# Analog_PI_Controller_v7.net
KiCad netlist of a schematic drawn in EasyEDA
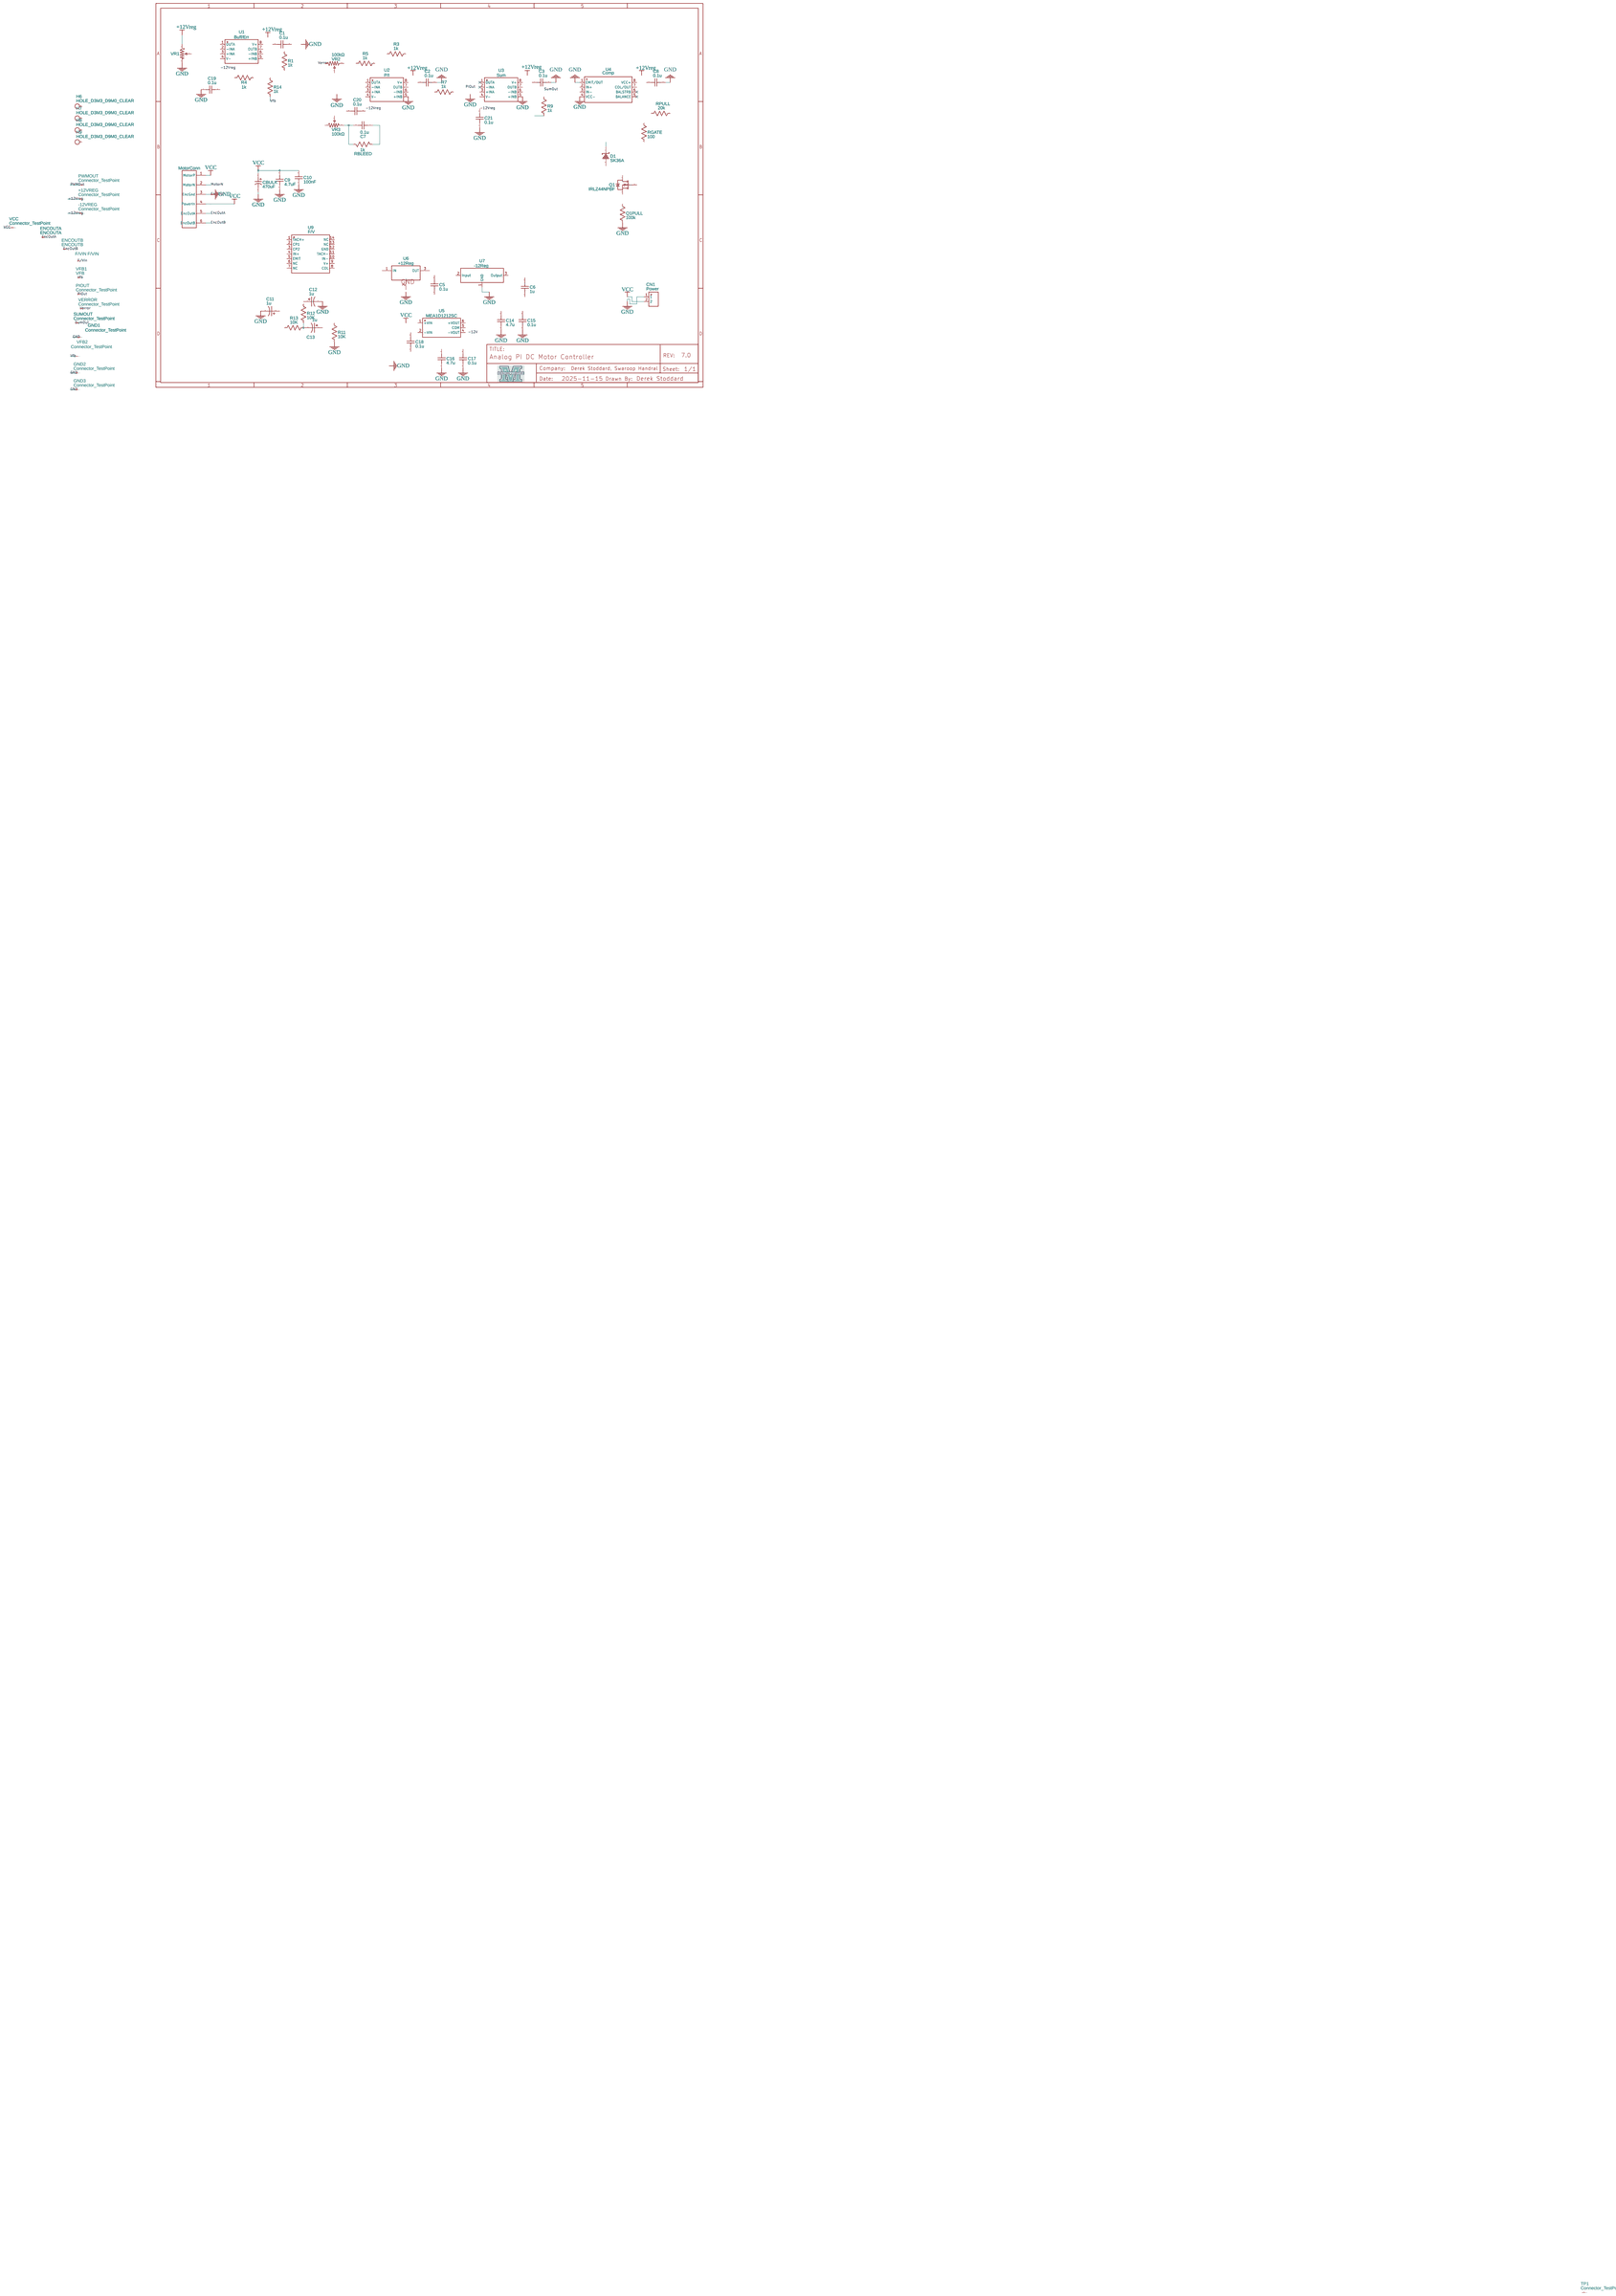
[diagram p0: schematic sheet]

(export (version "E")
  (design (tool "Eeschema 10.0.6"))
  (components
    (comp (ref "+12VREG") (value "Connector_TestPoint") (libsource (lib "") (part "Connector_TestPoint_8")))
    (comp (ref "-12VREG") (value "Connector_TestPoint") (libsource (lib "") (part "Connector_TestPoint_9")))
    (comp (ref "C1") (value "0.1u") (libsource (lib "") (part "C_0603_US_1")))
    (comp (ref "C2") (value "0.1u") (libsource (lib "") (part "C_0603_US_1")))
    (comp (ref "C3") (value "0.1u") (libsource (lib "") (part "C_0603_US_1")))
    (comp (ref "C5") (value "0.1u") (libsource (lib "") (part "C_0603_US")))
    (comp (ref "C6") (value "1u") (libsource (lib "") (part "C_0603_US")))
    (comp (ref "C7") (value "0.1u") (libsource (lib "") (part "C_0603_US_2")))
    (comp (ref "C8") (value "0.1u") (libsource (lib "") (part "C_0603_US_1")))
    (comp (ref "C9")
      (value "4.7uF")
      (fields
        (field (name "Manufacturer Part") "GRM188R61E475KE11D")
        (field (name "Manufacturer") "muRata(村田)")
      )
      (libsource (lib "") (part "GRM188R61E475KE11D"))
    )
    (comp (ref "C10")
      (value "100nF")
      (fields
        (field (name "Manufacturer Part") "GRM033R61E104KE14D")
        (field (name "Manufacturer") "muRata(村田)")
      )
      (libsource (lib "") (part "GRM033R61E104KE14D"))
    )
    (comp (ref "C11") (value "1u") (libsource (lib "") (part "C_Tan_SMD_A_US_2")))
    (comp (ref "C12") (value "1u") (libsource (lib "") (part "C_Tan_SMD_A_US_1")))
    (comp (ref "C13") (value "1u") (libsource (lib "") (part "C_Tan_SMD_A_US")))
    (comp (ref "C14") (value "4.7u") (libsource (lib "") (part "C_0603_US")))
    (comp (ref "C15") (value "0.1u") (libsource (lib "") (part "C_0603_US")))
    (comp (ref "C16") (value "4.7u") (libsource (lib "") (part "C_0603_US")))
    (comp (ref "C17") (value "0.1u") (libsource (lib "") (part "C_0603_US")))
    (comp (ref "C18") (value "0.1u") (libsource (lib "") (part "C_0603_US")))
    (comp (ref "C19") (value "0.1u") (libsource (lib "") (part "C_0603_US_1")))
    (comp (ref "C20") (value "0.1u") (libsource (lib "") (part "C_0603_US_1")))
    (comp (ref "C21") (value "0.1u") (libsource (lib "") (part "C_0603_US")))
    (comp (ref "CBULK")
      (value "470uF")
      (fields (field (name "Manufacturer Part") "EEEFN1V471UP") (field (name "Manufacturer") "PANASONIC(松下)"))
      (libsource (lib "") (part "EEEFN1V471UP"))
    )
    (comp (ref "CN1")
      (value "Power")
      (fields (field (name "Manufacturer Part") "691137710002") (field (name "Manufacturer") "Wurth(伍尔特)"))
      (libsource (lib "") (part "691137710002"))
    )
    (comp (ref "D1")
      (value "SK36A")
      (fields (field (name "Manufacturer Part") "SK36A-LTP") (field (name "Manufacturer") "MCC(美微科)"))
      (libsource (lib "") (part "SK36A-LTP"))
    )
    (comp (ref "ENCOUTA") (value "ENCOUTA") (libsource (lib "") (part "Connector_TestPoint_2")))
    (comp (ref "ENCOUTB") (value "ENCOUTB") (libsource (lib "") (part "Connector_TestPoint_1")))
    (comp (ref "F/VIN") (value "F/VIN") (libsource (lib "") (part "Connector_TestPoint_11")))
    (comp (ref "GND1") (value "Connector_TestPoint") (libsource (lib "") (part "Connector_TestPoint_4")))
    (comp (ref "GND2") (value "Connector_TestPoint") (libsource (lib "") (part "Connector_TestPoint_4")))
    (comp (ref "GND3") (value "Connector_TestPoint") (libsource (lib "") (part "Connector_TestPoint_4")))
    (comp (ref "H6") (value "HOLE_D3M3_D9M0_CLEAR") (libsource (lib "") (part "HOLE_D3M3_D9M0_CLEAR")))
    (comp (ref "H7") (value "HOLE_D3M3_D9M0_CLEAR") (libsource (lib "") (part "HOLE_D3M3_D9M0_CLEAR")))
    (comp (ref "H8") (value "HOLE_D3M3_D9M0_CLEAR") (libsource (lib "") (part "HOLE_D3M3_D9M0_CLEAR")))
    (comp (ref "H9") (value "HOLE_D3M3_D9M0_CLEAR") (libsource (lib "") (part "HOLE_D3M3_D9M0_CLEAR")))
    (comp (ref "MIN")
      (value "MotorConn")
      (fields (field (name "Manufacturer Part") "14110613002000") (field (name "Manufacturer") "Harting"))
      (libsource (lib "") (part "Harting 6P vertical"))
    )
    (comp (ref "PIOUT") (value "Connector_TestPoint") (libsource (lib "") (part "Connector_TestPoint_10")))
    (comp (ref "PWMOUT") (value "Connector_TestPoint") (libsource (lib "") (part "Connector_TestPoint_12")))
    (comp (ref "Q1")
      (value "IRLZ44NPBF")
      (fields (field (name "Manufacturer") "Infineon(英飞凌)"))
      (libsource (lib "") (part "IRLZ44NPBF"))
    )
    (comp (ref "Q1PULL") (value "100k") (libsource (lib "") (part "R_0603_US_6")))
    (comp (ref "R1") (value "1k") (libsource (lib "") (part "R_0603_US_2")))
    (comp (ref "R3") (value "1k") (libsource (lib "") (part "R_0603_US_1")))
    (comp (ref "R4") (value "1k") (libsource (lib "") (part "R_0603_US_5")))
    (comp (ref "R5") (value "1k") (libsource (lib "") (part "R_0603_US_1")))
    (comp (ref "R7") (value "1k") (libsource (lib "") (part "R_0603_US_5")))
    (comp (ref "R9") (value "1k") (libsource (lib "") (part "R_0603_US")))
    (comp (ref "R11") (value "10K") (libsource (lib "") (part "R_0603_US_2")))
    (comp (ref "R12") (value "10K") (libsource (lib "") (part "R_0603_US_2")))
    (comp (ref "R13") (value "10K") (libsource (lib "") (part "R_0603_US_1")))
    (comp (ref "R14") (value "1k") (libsource (lib "") (part "R_0603_US_2")))
    (comp (ref "RBLEED") (value "1k") (libsource (lib "") (part "R_0603_US_3")))
    (comp (ref "RGATE") (value "100") (libsource (lib "") (part "R_0603_US_7")))
    (comp (ref "RPULL") (value "20k") (libsource (lib "") (part "R_0603_US_4")))
    (comp (ref "SUMOUT") (value "Connector_TestPoint") (libsource (lib "") (part "Connector_TestPoint_5")))
    (comp (ref "TP1") (value "Connector_TestPoint") (libsource (lib "") (part "Connector_TestPoint_3")))
    (comp (ref "U1")
      (value "Buff/Err")
      (fields (field (name "Manufacturer Part") "OPA2197ID") (field (name "Manufacturer") "TI(德州仪器)"))
      (libsource (lib "") (part "OPA2197ID"))
    )
    (comp (ref "U2")
      (value "P/I")
      (fields (field (name "Manufacturer Part") "OPA2197ID") (field (name "Manufacturer") "TI(德州仪器)"))
      (libsource (lib "") (part "OPA2197ID"))
    )
    (comp (ref "U3")
      (value "Sum")
      (fields (field (name "Manufacturer Part") "OPA2197ID") (field (name "Manufacturer") "TI(德州仪器)"))
      (libsource (lib "") (part "OPA2197ID"))
    )
    (comp (ref "U4")
      (value "Comp")
      (fields (field (name "Manufacturer Part") "LM311DR") (field (name "Manufacturer") "TI(德州仪器)"))
      (libsource (lib "") (part "LM311DR"))
    )
    (comp (ref "U5")
      (value "MEA1D1212SC")
      (fields (field (name "Manufacturer") "YLPTEC(易川)"))
      (libsource (lib "") (part "MEA1D1212SC"))
    )
    (comp (ref "U6")
      (value "+12Reg")
      (fields (field (name "Manufacturer Part") "LM7812CT/NOPB") (field (name "Manufacturer") "TI(德州仪器)"))
      (libsource (lib "") (part "LM7812CT/NOPB"))
    )
    (comp (ref "U7")
      (value "-12Reg")
      (fields (field (name "Manufacturer Part") "LM7912CT/NOPB") (field (name "Manufacturer") "TI(德州仪器)"))
      (libsource (lib "") (part "LM7912CT/NOPB"))
    )
    (comp (ref "U9")
      (value "F/V")
      (fields (field (name "Manufacturer Part") "LM2917MX/NOPB") (field (name "Manufacturer") "TI(德州仪器)"))
      (libsource (lib "") (part "LM2917MX/NOPB"))
    )
    (comp (ref "VCC") (value "Connector_TestPoint") (libsource (lib "") (part "Connector_TestPoint_7")))
    (comp (ref "VERROR") (value "Connector_TestPoint") (libsource (lib "") (part "Connector_TestPoint_6")))
    (comp (ref "VFB1") (value "VFB") (libsource (lib "") (part "Connector_TestPoint")))
    (comp (ref "VFB2") (value "Connector_TestPoint") (libsource (lib "") (part "Connector_TestPoint")))
    (comp (ref "VR1")
      (value "PTV09A-4020U-B104")
      (fields (field (name "Manufacturer") "Bourns Inc."))
      (libsource (lib "") (part "PTV09A-4020U-B104"))
    )
    (comp (ref "VR2")
      (value "100kΩ")
      (fields (field (name "Manufacturer Part") "PVG5A104C03R00") (field (name "Manufacturer") "BOURNS"))
      (libsource (lib "") (part "PVG5A104C03R00"))
    )
    (comp (ref "VR3")
      (value "100kΩ")
      (fields (field (name "Manufacturer Part") "PVG5A104C03R00") (field (name "Manufacturer") "BOURNS"))
      (libsource (lib "") (part "PVG5A104C03R00_1"))
    )
  )
  (nets
    (net (code "1") (name "+12Vreg") (class "Default")
      (node (ref "+12VREG") (pin "1") (pinfunction "1_1") (pintype "unspecified"))
      (node (ref "VR1") (pin "1") (pinfunction "1_1") (pintype "unspecified"))
    )
    (net (code "3") (name "/-12Vreg") (class "Default")
      (node (ref "-12VREG") (pin "1") (pinfunction "1_1") (pintype "unspecified"))
      (node (ref "C21") (pin "2") (pinfunction "2_2") (pintype "unspecified"))
    )
    (net (code "4") (name "/EncOutA") (class "Default")
      (node (ref "ENCOUTA") (pin "1") (pinfunction "1_1") (pintype "unspecified"))
      (node (ref "MIN") (pin "5") (pinfunction "EncOutA_5") (pintype "output"))
    )
    (net (code "5") (name "/EncOutB") (class "Default")
      (node (ref "ENCOUTB") (pin "1") (pinfunction "1_1") (pintype "unspecified"))
      (node (ref "MIN") (pin "6") (pinfunction "EncOutB_6") (pintype "output"))
    )
    (net (code "6") (name "/F{slash}VIn") (class "Default")
      (node (ref "F/VIN") (pin "1") (pinfunction "1_1") (pintype "unspecified"))
    )
    (net (code "7") (name "/MotorN") (class "Default")
      (node (ref "MIN") (pin "2") (pinfunction "MotorN_2") (pintype "passive"))
    )
    (net (code "8") (name "/PIOut") (class "Default")
      (node (ref "PIOUT") (pin "1") (pinfunction "1_1") (pintype "unspecified"))
    )
    (net (code "9") (name "/PWMOut") (class "Default")
      (node (ref "PWMOUT") (pin "1") (pinfunction "1_1") (pintype "unspecified"))
    )
    (net (code "10") (name "/SumOut") (class "Default")
      (node (ref "SUMOUT") (pin "1") (pinfunction "1_1") (pintype "unspecified"))
    )
    (net (code "11") (name "/Verror") (class "Default")
      (node (ref "VERROR") (pin "1") (pinfunction "1_1") (pintype "unspecified"))
    )
    (net (code "12") (name "/Vfb") (class "Default")
      (node (ref "R14") (pin "1") (pinfunction "1_1") (pintype "unspecified"))
      (node (ref "VFB1") (pin "1") (pinfunction "1_1") (pintype "unspecified"))
      (node (ref "VFB2") (pin "1") (pinfunction "1_1") (pintype "unspecified"))
    )
    (net (code "13") (name "GND") (class "Default")
      (node (ref "C10") (pin "1") (pinfunction "1_1") (pintype "input"))
      (node (ref "C11") (pin "2") (pinfunction "2_2") (pintype "unspecified"))
      (node (ref "C12") (pin "2") (pinfunction "2_2") (pintype "unspecified"))
      (node (ref "C14") (pin "1") (pinfunction "1_1") (pintype "unspecified"))
      (node (ref "C15") (pin "1") (pinfunction "1_1") (pintype "unspecified"))
      (node (ref "C16") (pin "1") (pinfunction "1_1") (pintype "unspecified"))
      (node (ref "C17") (pin "1") (pinfunction "1_1") (pintype "unspecified"))
      (node (ref "C19") (pin "1") (pinfunction "1_1") (pintype "unspecified"))
      (node (ref "C2") (pin "2") (pinfunction "2_2") (pintype "unspecified"))
      (node (ref "C21") (pin "1") (pinfunction "1_1") (pintype "unspecified"))
      (node (ref "C3") (pin "2") (pinfunction "2_2") (pintype "unspecified"))
      (node (ref "C8") (pin "2") (pinfunction "2_2") (pintype "unspecified"))
      (node (ref "C9") (pin "1") (pinfunction "1_1") (pintype "unspecified"))
      (node (ref "CBULK") (pin "2") (pinfunction "2_2") (pintype "input"))
      (node (ref "CN1") (pin "1") (pinfunction "1_1") (pintype "unspecified"))
      (node (ref "GND1") (pin "1") (pinfunction "1_1") (pintype "unspecified"))
      (node (ref "GND2") (pin "1") (pinfunction "1_1") (pintype "unspecified"))
      (node (ref "GND3") (pin "1") (pinfunction "1_1") (pintype "unspecified"))
      (node (ref "MIN") (pin "3") (pinfunction "EncGnd_3") (pintype "unspecified"))
      (node (ref "Q1PULL") (pin "2") (pinfunction "2_2") (pintype "unspecified"))
      (node (ref "R11") (pin "1") (pinfunction "1_1") (pintype "unspecified"))
      (node (ref "U2") (pin "5") (pinfunction "+INB_5") (pintype "unspecified"))
      (node (ref "U3") (pin "5") (pinfunction "+INB_5") (pintype "unspecified"))
      (node (ref "U4") (pin "1") (pinfunction "EMIT/OUT_1") (pintype "unspecified"))
      (node (ref "U4") (pin "4") (pinfunction "VCC-_4") (pintype "unspecified"))
      (node (ref "U7") (pin "1") (pinfunction "GND_1") (pintype "unspecified"))
      (node (ref "VR1") (pin "3") (pinfunction "3_3") (pintype "unspecified"))
    )
    (net (code "14") (name "Net-(C7-Pad1)") (class "Default")
      (node (ref "C7") (pin "1") (pinfunction "1_1") (pintype "unspecified"))
      (node (ref "RBLEED") (pin "2") (pinfunction "2_2") (pintype "unspecified"))
    )
    (net (code "15") (name "Net-(C7-Pad2)") (class "Default")
      (node (ref "C7") (pin "2") (pinfunction "2_2") (pintype "unspecified"))
      (node (ref "RBLEED") (pin "1") (pinfunction "1_1") (pintype "unspecified"))
      (node (ref "VR3") (pin "3") (pinfunction "3_3") (pintype "unspecified"))
    )
    (net (code "16") (name "Net-(C13-Pad2)") (class "Default")
      (node (ref "C13") (pin "2") (pinfunction "2_2") (pintype "unspecified"))
      (node (ref "R12") (pin "1") (pinfunction "1_1") (pintype "unspecified"))
      (node (ref "R13") (pin "1") (pinfunction "1_1") (pintype "unspecified"))
    )
    (net (code "17") (name "VCC") (class "Default")
      (node (ref "C10") (pin "2") (pinfunction "2_2") (pintype "input"))
      (node (ref "C9") (pin "2") (pinfunction "2_2") (pintype "unspecified"))
      (node (ref "CBULK") (pin "1") (pinfunction "1_1") (pintype "input"))
      (node (ref "CN1") (pin "2") (pinfunction "2_2") (pintype "unspecified"))
      (node (ref "MIN") (pin "1") (pinfunction "MotorP_1") (pintype "passive"))
      (node (ref "MIN") (pin "4") (pinfunction "PowerIn_4") (pintype "passive"))
      (node (ref "VCC") (pin "1") (pinfunction "1_1") (pintype "unspecified"))
    )
    (net (code "18") (name "unconnected-(C1-Pad1)") (class "Default")
      (node (ref "C1") (pin "1") (pinfunction "1_1") (pintype "unspecified"))
    )
    (net (code "19") (name "unconnected-(C1-Pad2)") (class "Default")
      (node (ref "C1") (pin "2") (pinfunction "2_2") (pintype "unspecified"))
    )
    (net (code "20") (name "unconnected-(C2-Pad1)") (class "Default")
      (node (ref "C2") (pin "1") (pinfunction "1_1") (pintype "unspecified"))
    )
    (net (code "21") (name "unconnected-(C3-Pad1)") (class "Default")
      (node (ref "C3") (pin "1") (pinfunction "1_1") (pintype "unspecified"))
    )
    (net (code "22") (name "unconnected-(C5-Pad1)") (class "Default")
      (node (ref "C5") (pin "1") (pinfunction "1_1") (pintype "unspecified"))
    )
    (net (code "23") (name "unconnected-(C5-Pad2)") (class "Default")
      (node (ref "C5") (pin "2") (pinfunction "2_2") (pintype "unspecified"))
    )
    (net (code "24") (name "unconnected-(C6-Pad1)") (class "Default")
      (node (ref "C6") (pin "1") (pinfunction "1_1") (pintype "unspecified"))
    )
    (net (code "25") (name "unconnected-(C6-Pad2)") (class "Default")
      (node (ref "C6") (pin "2") (pinfunction "2_2") (pintype "unspecified"))
    )
    (net (code "26") (name "unconnected-(C8-Pad1)") (class "Default")
      (node (ref "C8") (pin "1") (pinfunction "1_1") (pintype "unspecified"))
    )
    (net (code "27") (name "unconnected-(C11-Pad1)") (class "Default")
      (node (ref "C11") (pin "1") (pinfunction "1_1") (pintype "unspecified"))
    )
    (net (code "28") (name "unconnected-(C12-Pad1)") (class "Default")
      (node (ref "C12") (pin "1") (pinfunction "1_1") (pintype "unspecified"))
    )
    (net (code "29") (name "unconnected-(C13-Pad1)") (class "Default")
      (node (ref "C13") (pin "1") (pinfunction "1_1") (pintype "unspecified"))
    )
    (net (code "30") (name "unconnected-(C14-Pad2)") (class "Default")
      (node (ref "C14") (pin "2") (pinfunction "2_2") (pintype "unspecified"))
    )
    (net (code "31") (name "unconnected-(C15-Pad2)") (class "Default")
      (node (ref "C15") (pin "2") (pinfunction "2_2") (pintype "unspecified"))
    )
    (net (code "32") (name "unconnected-(C16-Pad2)") (class "Default")
      (node (ref "C16") (pin "2") (pinfunction "2_2") (pintype "unspecified"))
    )
    (net (code "33") (name "unconnected-(C17-Pad2)") (class "Default")
      (node (ref "C17") (pin "2") (pinfunction "2_2") (pintype "unspecified"))
    )
    (net (code "34") (name "unconnected-(C18-Pad1)") (class "Default")
      (node (ref "C18") (pin "1") (pinfunction "1_1") (pintype "unspecified"))
    )
    (net (code "35") (name "unconnected-(C18-Pad2)") (class "Default")
      (node (ref "C18") (pin "2") (pinfunction "2_2") (pintype "unspecified"))
    )
    (net (code "36") (name "unconnected-(C19-Pad2)") (class "Default")
      (node (ref "C19") (pin "2") (pinfunction "2_2") (pintype "unspecified"))
    )
    (net (code "37") (name "unconnected-(C20-Pad1)") (class "Default")
      (node (ref "C20") (pin "1") (pinfunction "1_1") (pintype "unspecified"))
    )
    (net (code "38") (name "unconnected-(C20-Pad2)") (class "Default")
      (node (ref "C20") (pin "2") (pinfunction "2_2") (pintype "unspecified"))
    )
    (net (code "39") (name "unconnected-(D1-A-Pad2)") (class "Default")
      (node (ref "D1") (pin "2") (pinfunction "A_2") (pintype "unspecified"))
    )
    (net (code "40") (name "unconnected-(D1-K-Pad1)") (class "Default")
      (node (ref "D1") (pin "1") (pinfunction "K_1") (pintype "unspecified"))
    )
    (net (code "41") (name "unconnected-(H6-Pad1)") (class "Default")
      (node (ref "H6") (pin "1") (pinfunction "1_1") (pintype "unspecified"))
    )
    (net (code "42") (name "unconnected-(H7-Pad1)") (class "Default")
      (node (ref "H7") (pin "1") (pinfunction "1_1") (pintype "unspecified"))
    )
    (net (code "43") (name "unconnected-(H8-Pad1)") (class "Default")
      (node (ref "H8") (pin "1") (pinfunction "1_1") (pintype "unspecified"))
    )
    (net (code "44") (name "unconnected-(H9-Pad1)") (class "Default")
      (node (ref "H9") (pin "1") (pinfunction "1_1") (pintype "unspecified"))
    )
    (net (code "45") (name "unconnected-(Q1-D-Pad2)") (class "Default")
      (node (ref "Q1") (pin "2") (pinfunction "D_2") (pintype "unspecified"))
    )
    (net (code "46") (name "unconnected-(Q1-G-Pad1)") (class "Default")
      (node (ref "Q1") (pin "1") (pinfunction "G_1") (pintype "unspecified"))
    )
    (net (code "47") (name "unconnected-(Q1-S-Pad3)") (class "Default")
      (node (ref "Q1") (pin "3") (pinfunction "S_3") (pintype "unspecified"))
    )
    (net (code "48") (name "unconnected-(Q1PULL-Pad1)") (class "Default")
      (node (ref "Q1PULL") (pin "1") (pinfunction "1_1") (pintype "unspecified"))
    )
    (net (code "49") (name "unconnected-(R1-Pad1)") (class "Default")
      (node (ref "R1") (pin "1") (pinfunction "1_1") (pintype "unspecified"))
    )
    (net (code "50") (name "unconnected-(R1-Pad2)") (class "Default")
      (node (ref "R1") (pin "2") (pinfunction "2_2") (pintype "unspecified"))
    )
    (net (code "51") (name "unconnected-(R3-Pad1)") (class "Default")
      (node (ref "R3") (pin "1") (pinfunction "1_1") (pintype "unspecified"))
    )
    (net (code "52") (name "unconnected-(R3-Pad2)") (class "Default")
      (node (ref "R3") (pin "2") (pinfunction "2_2") (pintype "unspecified"))
    )
    (net (code "53") (name "unconnected-(R4-Pad1)") (class "Default")
      (node (ref "R4") (pin "1") (pinfunction "1_1") (pintype "unspecified"))
    )
    (net (code "54") (name "unconnected-(R4-Pad2)") (class "Default")
      (node (ref "R4") (pin "2") (pinfunction "2_2") (pintype "unspecified"))
    )
    (net (code "55") (name "unconnected-(R5-Pad1)") (class "Default")
      (node (ref "R5") (pin "1") (pinfunction "1_1") (pintype "unspecified"))
    )
    (net (code "56") (name "unconnected-(R5-Pad2)") (class "Default")
      (node (ref "R5") (pin "2") (pinfunction "2_2") (pintype "unspecified"))
    )
    (net (code "57") (name "unconnected-(R7-Pad1)") (class "Default")
      (node (ref "R7") (pin "1") (pinfunction "1_1") (pintype "unspecified"))
    )
    (net (code "58") (name "unconnected-(R7-Pad2)") (class "Default")
      (node (ref "R7") (pin "2") (pinfunction "2_2") (pintype "unspecified"))
    )
    (net (code "59") (name "unconnected-(R9-Pad1)") (class "Default")
      (node (ref "R9") (pin "1") (pinfunction "1_1") (pintype "unspecified"))
    )
    (net (code "60") (name "unconnected-(R9-Pad2)") (class "Default")
      (node (ref "R9") (pin "2") (pinfunction "2_2") (pintype "unspecified"))
    )
    (net (code "61") (name "unconnected-(R11-Pad2)") (class "Default")
      (node (ref "R11") (pin "2") (pinfunction "2_2") (pintype "unspecified"))
    )
    (net (code "62") (name "unconnected-(R12-Pad2)") (class "Default")
      (node (ref "R12") (pin "2") (pinfunction "2_2") (pintype "unspecified"))
    )
    (net (code "63") (name "unconnected-(R13-Pad2)") (class "Default")
      (node (ref "R13") (pin "2") (pinfunction "2_2") (pintype "unspecified"))
    )
    (net (code "64") (name "unconnected-(R14-Pad2)") (class "Default")
      (node (ref "R14") (pin "2") (pinfunction "2_2") (pintype "unspecified"))
    )
    (net (code "65") (name "unconnected-(RGATE-Pad1)") (class "Default")
      (node (ref "RGATE") (pin "1") (pinfunction "1_1") (pintype "unspecified"))
    )
    (net (code "66") (name "unconnected-(RGATE-Pad2)") (class "Default")
      (node (ref "RGATE") (pin "2") (pinfunction "2_2") (pintype "unspecified"))
    )
    (net (code "67") (name "unconnected-(RPULL-Pad1)") (class "Default")
      (node (ref "RPULL") (pin "1") (pinfunction "1_1") (pintype "unspecified"))
    )
    (net (code "68") (name "unconnected-(RPULL-Pad2)") (class "Default")
      (node (ref "RPULL") (pin "2") (pinfunction "2_2") (pintype "unspecified"))
    )
    (net (code "69") (name "unconnected-(TP1-Pad1)") (class "Default")
      (node (ref "TP1") (pin "1") (pinfunction "1_1") (pintype "unspecified"))
    )
    (net (code "70") (name "unconnected-(U1-+INA-Pad3)") (class "Default")
      (node (ref "U1") (pin "3") (pinfunction "+INA_3") (pintype "unspecified"))
    )
    (net (code "71") (name "unconnected-(U1-+INB-Pad5)") (class "Default")
      (node (ref "U1") (pin "5") (pinfunction "+INB_5") (pintype "unspecified"))
    )
    (net (code "72") (name "unconnected-(U1--INA-Pad2)") (class "Default")
      (node (ref "U1") (pin "2") (pinfunction "-INA_2") (pintype "unspecified"))
    )
    (net (code "73") (name "unconnected-(U1--INB-Pad6)") (class "Default")
      (node (ref "U1") (pin "6") (pinfunction "-INB_6") (pintype "unspecified"))
    )
    (net (code "74") (name "unconnected-(U1-OUTA-Pad1)") (class "Default")
      (node (ref "U1") (pin "1") (pinfunction "OUTA_1") (pintype "unspecified"))
    )
    (net (code "75") (name "unconnected-(U1-OUTB-Pad7)") (class "Default")
      (node (ref "U1") (pin "7") (pinfunction "OUTB_7") (pintype "unspecified"))
    )
    (net (code "76") (name "unconnected-(U1-V+-Pad8)") (class "Default")
      (node (ref "U1") (pin "8") (pinfunction "V+_8") (pintype "unspecified"))
    )
    (net (code "77") (name "unconnected-(U1-V--Pad4)") (class "Default")
      (node (ref "U1") (pin "4") (pinfunction "V-_4") (pintype "unspecified"))
    )
    (net (code "78") (name "unconnected-(U2-+INA-Pad3)") (class "Default")
      (node (ref "U2") (pin "3") (pinfunction "+INA_3") (pintype "unspecified"))
    )
    (net (code "79") (name "unconnected-(U2--INA-Pad2)") (class "Default")
      (node (ref "U2") (pin "2") (pinfunction "-INA_2") (pintype "unspecified"))
    )
    (net (code "80") (name "unconnected-(U2--INB-Pad6)") (class "Default")
      (node (ref "U2") (pin "6") (pinfunction "-INB_6") (pintype "unspecified"))
    )
    (net (code "81") (name "unconnected-(U2-OUTA-Pad1)") (class "Default")
      (node (ref "U2") (pin "1") (pinfunction "OUTA_1") (pintype "unspecified"))
    )
    (net (code "82") (name "unconnected-(U2-OUTB-Pad7)") (class "Default")
      (node (ref "U2") (pin "7") (pinfunction "OUTB_7") (pintype "unspecified"))
    )
    (net (code "83") (name "unconnected-(U2-V+-Pad8)") (class "Default")
      (node (ref "U2") (pin "8") (pinfunction "V+_8") (pintype "unspecified"))
    )
    (net (code "84") (name "unconnected-(U2-V--Pad4)") (class "Default")
      (node (ref "U2") (pin "4") (pinfunction "V-_4") (pintype "unspecified"))
    )
    (net (code "85") (name "unconnected-(U3-+INA-Pad3)") (class "Default")
      (node (ref "U3") (pin "3") (pinfunction "+INA_3") (pintype "unspecified"))
    )
    (net (code "86") (name "unconnected-(U3--INA-Pad2)") (class "Default")
      (node (ref "U3") (pin "2") (pinfunction "-INA_2") (pintype "unspecified+no_connect"))
    )
    (net (code "87") (name "unconnected-(U3--INB-Pad6)") (class "Default")
      (node (ref "U3") (pin "6") (pinfunction "-INB_6") (pintype "unspecified"))
    )
    (net (code "88") (name "unconnected-(U3-OUTA-Pad1)") (class "Default")
      (node (ref "U3") (pin "1") (pinfunction "OUTA_1") (pintype "unspecified+no_connect"))
    )
    (net (code "89") (name "unconnected-(U3-OUTB-Pad7)") (class "Default")
      (node (ref "U3") (pin "7") (pinfunction "OUTB_7") (pintype "unspecified"))
    )
    (net (code "90") (name "unconnected-(U3-V+-Pad8)") (class "Default")
      (node (ref "U3") (pin "8") (pinfunction "V+_8") (pintype "unspecified"))
    )
    (net (code "91") (name "unconnected-(U3-V--Pad4)") (class "Default")
      (node (ref "U3") (pin "4") (pinfunction "V-_4") (pintype "unspecified"))
    )
    (net (code "92") (name "unconnected-(U4-BALANCE-Pad5)") (class "Default")
      (node (ref "U4") (pin "5") (pinfunction "BALANCE_5") (pintype "unspecified+no_connect"))
    )
    (net (code "93") (name "unconnected-(U4-BALSTRB-Pad6)") (class "Default")
      (node (ref "U4") (pin "6") (pinfunction "BALSTRB_6") (pintype "unspecified+no_connect"))
    )
    (net (code "94") (name "unconnected-(U4-COL{slash}OUT-Pad7)") (class "Default")
      (node (ref "U4") (pin "7") (pinfunction "COL/OUT_7") (pintype "unspecified"))
    )
    (net (code "95") (name "unconnected-(U4-IN+-Pad2)") (class "Default")
      (node (ref "U4") (pin "2") (pinfunction "IN+_2") (pintype "unspecified"))
    )
    (net (code "96") (name "unconnected-(U4-IN--Pad3)") (class "Default")
      (node (ref "U4") (pin "3") (pinfunction "IN-_3") (pintype "unspecified"))
    )
    (net (code "97") (name "unconnected-(U4-VCC+-Pad8)") (class "Default")
      (node (ref "U4") (pin "8") (pinfunction "VCC+_8") (pintype "unspecified"))
    )
    (net (code "98") (name "unconnected-(U5-+VIN-Pad1)") (class "Default")
      (node (ref "U5") (pin "1") (pinfunction "+VIN_1") (pintype "unspecified"))
    )
    (net (code "99") (name "unconnected-(U5-+VOUT-Pad6)") (class "Default")
      (node (ref "U5") (pin "6") (pinfunction "+VOUT_6") (pintype "unspecified"))
    )
    (net (code "100") (name "unconnected-(U5--VIN-Pad2)") (class "Default")
      (node (ref "U5") (pin "2") (pinfunction "-VIN_2") (pintype "unspecified"))
    )
    (net (code "101") (name "unconnected-(U5--VOUT-Pad4)") (class "Default")
      (node (ref "U5") (pin "4") (pinfunction "-VOUT_4") (pintype "unspecified"))
    )
    (net (code "102") (name "unconnected-(U5-COM-Pad5)") (class "Default")
      (node (ref "U5") (pin "5") (pinfunction "COM_5") (pintype "unspecified"))
    )
    (net (code "103") (name "unconnected-(U6-GND-Pad2)") (class "Default")
      (node (ref "U6") (pin "2") (pinfunction "GND_2") (pintype "passive"))
    )
    (net (code "104") (name "unconnected-(U6-IN-Pad1)") (class "Default")
      (node (ref "U6") (pin "1") (pinfunction "IN_1") (pintype "passive"))
    )
    (net (code "105") (name "unconnected-(U6-OUT-Pad3)") (class "Default")
      (node (ref "U6") (pin "3") (pinfunction "OUT_3") (pintype "passive"))
    )
    (net (code "106") (name "unconnected-(U7-Input-Pad2)") (class "Default")
      (node (ref "U7") (pin "2") (pinfunction "Input_2") (pintype "unspecified"))
    )
    (net (code "107") (name "unconnected-(U7-Output-Pad3)") (class "Default")
      (node (ref "U7") (pin "3") (pinfunction "Output_3") (pintype "unspecified"))
    )
    (net (code "108") (name "unconnected-(U9-COL-Pad8)") (class "Default")
      (node (ref "U9") (pin "8") (pinfunction "COL_8") (pintype "unspecified"))
    )
    (net (code "109") (name "unconnected-(U9-CP1-Pad2)") (class "Default")
      (node (ref "U9") (pin "2") (pinfunction "CP1_2") (pintype "unspecified"))
    )
    (net (code "110") (name "unconnected-(U9-CP2-Pad3)") (class "Default")
      (node (ref "U9") (pin "3") (pinfunction "CP2_3") (pintype "unspecified"))
    )
    (net (code "111") (name "unconnected-(U9-EMIT-Pad5)") (class "Default")
      (node (ref "U9") (pin "5") (pinfunction "EMIT_5") (pintype "unspecified"))
    )
    (net (code "112") (name "unconnected-(U9-GND-Pad12)") (class "Default")
      (node (ref "U9") (pin "12") (pinfunction "GND_12") (pintype "unspecified"))
    )
    (net (code "113") (name "unconnected-(U9-IN+-Pad4)") (class "Default")
      (node (ref "U9") (pin "4") (pinfunction "IN+_4") (pintype "unspecified"))
    )
    (net (code "114") (name "unconnected-(U9-IN--Pad10)") (class "Default")
      (node (ref "U9") (pin "10") (pinfunction "IN-_10") (pintype "unspecified"))
    )
    (net (code "115") (name "unconnected-(U9-NC-Pad6)") (class "Default")
      (node (ref "U9") (pin "6") (pinfunction "NC_6") (pintype "unspecified"))
    )
    (net (code "116") (name "unconnected-(U9-NC-Pad7)") (class "Default")
      (node (ref "U9") (pin "7") (pinfunction "NC_7") (pintype "unspecified"))
    )
    (net (code "117") (name "unconnected-(U9-NC-Pad13)") (class "Default")
      (node (ref "U9") (pin "13") (pinfunction "NC_13") (pintype "unspecified"))
    )
    (net (code "118") (name "unconnected-(U9-NC-Pad14)") (class "Default")
      (node (ref "U9") (pin "14") (pinfunction "NC_14") (pintype "unspecified"))
    )
    (net (code "119") (name "unconnected-(U9-TACH+-Pad1)") (class "Default")
      (node (ref "U9") (pin "1") (pinfunction "TACH+_1") (pintype "unspecified"))
    )
    (net (code "120") (name "unconnected-(U9-TACH--Pad11)") (class "Default")
      (node (ref "U9") (pin "11") (pinfunction "TACH-_11") (pintype "unspecified"))
    )
    (net (code "121") (name "unconnected-(U9-V+-Pad9)") (class "Default")
      (node (ref "U9") (pin "9") (pinfunction "V+_9") (pintype "unspecified"))
    )
    (net (code "122") (name "unconnected-(VR1-Pad2)") (class "Default")
      (node (ref "VR1") (pin "2") (pinfunction "2_2") (pintype "unspecified"))
    )
    (net (code "123") (name "unconnected-(VR2-Pad1)") (class "Default")
      (node (ref "VR2") (pin "1") (pinfunction "1_1") (pintype "unspecified"))
    )
    (net (code "124") (name "unconnected-(VR2-Pad2)") (class "Default")
      (node (ref "VR2") (pin "2") (pinfunction "2_2") (pintype "unspecified"))
    )
    (net (code "125") (name "unconnected-(VR2-Pad3)") (class "Default")
      (node (ref "VR2") (pin "3") (pinfunction "3_3") (pintype "unspecified"))
    )
    (net (code "126") (name "unconnected-(VR3-Pad1)") (class "Default")
      (node (ref "VR3") (pin "1") (pinfunction "1_1") (pintype "unspecified"))
    )
    (net (code "127") (name "unconnected-(VR3-Pad2)") (class "Default")
      (node (ref "VR3") (pin "2") (pinfunction "2_2") (pintype "unspecified"))
    )
  )
)
